# Saules_kolektoriaus_valdiklis_v1_21.net
KiCad netlist of a schematic drawn in EAGLE
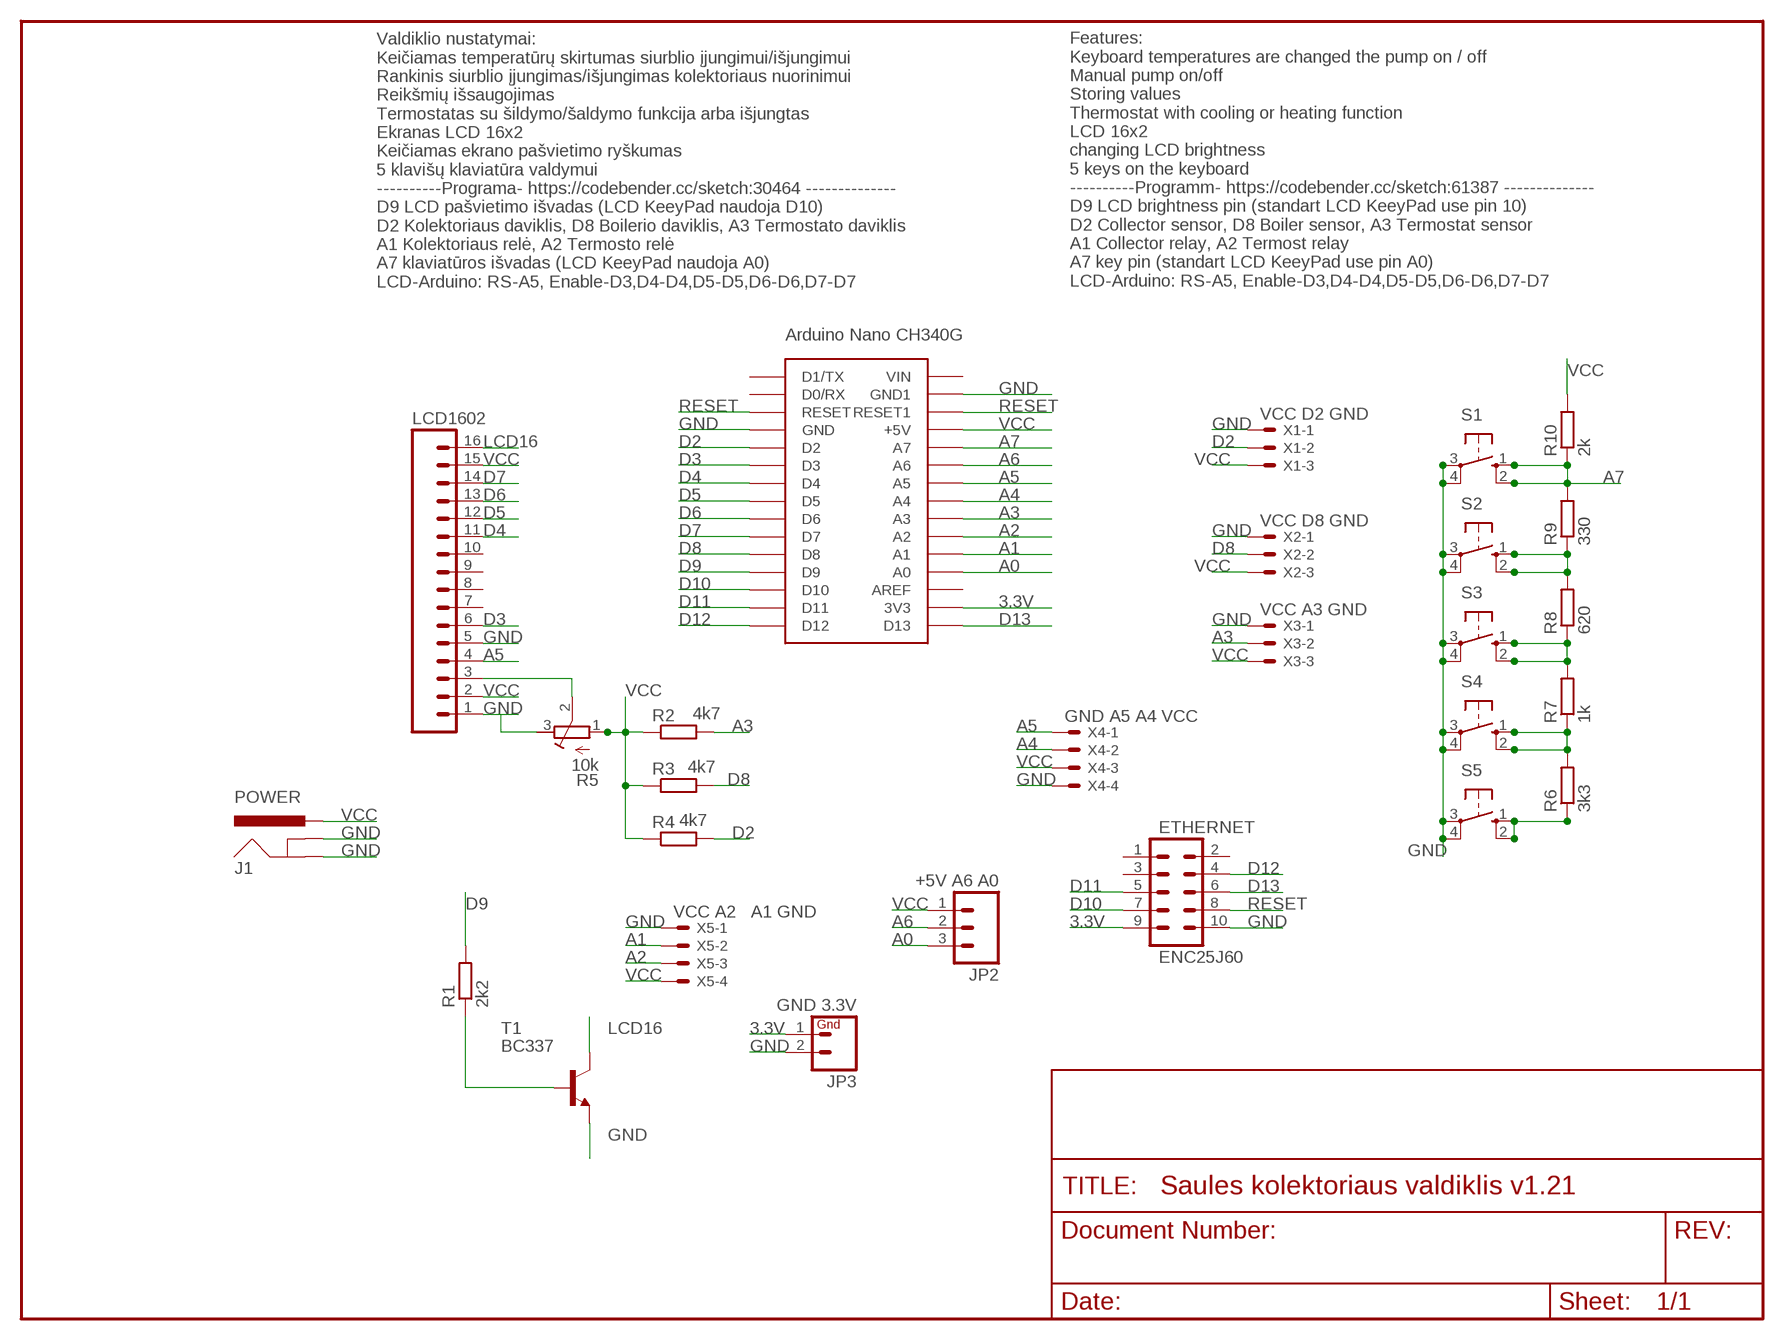
[diagram p0: schematic, sheet 1]

(export (version "E")
  (design (tool "Eeschema 10.0.6"))
  (components
    (comp (ref "ARDUINONANOCH340G")
      (value "ARDUINONANO")
      (footprint "eagle-import:PDIP-32")
      (libsource (lib "eagle-import") (part "ARDUINONANO"))
    )
    (comp (ref "ETHERNET")
      (value "ENC25J60")
      (footprint "eagle-import:AVR_ICSP")
      (libsource (lib "eagle-import") (part "M05X2PTH"))
    )
    (comp (ref "J1")
      (value "POWER")
      (footprint "eagle-import:POWER_JACK_PTH_LOCK")
      (libsource (lib "eagle-import") (part "POWER_JACKPTH_LOCK"))
    )
    (comp (ref "JP2")
      (value "+5V A6 A0")
      (footprint "eagle-import:1X03")
      (libsource (lib "eagle-import") (part "M03PTH"))
    )
    (comp (ref "JP3")
      (value "GND 3.3V")
      (footprint "eagle-import:1X02")
      (libsource (lib "eagle-import") (part "M02PTH"))
    )
    (comp (ref "LCD1602")
      (value "HEADER-16P-2.54")
      (footprint "eagle-import:16P-2.54")
      (libsource (lib "eagle-import") (part "HEADER-16P-2.54"))
    )
    (comp (ref "R1")
      (value "2k2")
      (footprint "eagle-import:0207_10")
      (libsource (lib "eagle-import") (part "R-EU_0207/10"))
    )
    (comp (ref "R2")
      (value "4k7")
      (footprint "eagle-import:0207_10")
      (libsource (lib "eagle-import") (part "R-EU_0207/10"))
    )
    (comp (ref "R3")
      (value "4k7")
      (footprint "eagle-import:0207_10")
      (libsource (lib "eagle-import") (part "R-EU_0207/10"))
    )
    (comp (ref "R4")
      (value "4k7")
      (footprint "eagle-import:0207_10")
      (libsource (lib "eagle-import") (part "R-EU_0207/10"))
    )
    (comp (ref "R5")
      (value "10k")
      (footprint "eagle-import:RTRIM64W")
      (libsource (lib "eagle-import") (part "R-TRIMM64W"))
    )
    (comp (ref "R6")
      (value "3k3")
      (footprint "eagle-import:0207_10")
      (libsource (lib "eagle-import") (part "R-EU_0207/10"))
    )
    (comp (ref "R7")
      (value "1k")
      (footprint "eagle-import:0207_10")
      (libsource (lib "eagle-import") (part "R-EU_0207/10"))
    )
    (comp (ref "R8")
      (value "620")
      (footprint "eagle-import:0207_10")
      (libsource (lib "eagle-import") (part "R-EU_0207/10"))
    )
    (comp (ref "R9")
      (value "330")
      (footprint "eagle-import:0207_10")
      (libsource (lib "eagle-import") (part "R-EU_0207/10"))
    )
    (comp (ref "R10")
      (value "2k")
      (footprint "eagle-import:0207_10")
      (libsource (lib "eagle-import") (part "R-EU_0207/10"))
    )
    (comp (ref "S1")
      (value "10-XX")
      (footprint "eagle-import:B3F-10XX")
      (fields (field (name "MPN") "B3F-1000"))
      (libsource (lib "eagle-import") (part "10-XX"))
    )
    (comp (ref "S2")
      (value "10-XX")
      (footprint "eagle-import:B3F-10XX")
      (fields (field (name "MPN") "B3F-1000"))
      (libsource (lib "eagle-import") (part "10-XX"))
    )
    (comp (ref "S3")
      (value "10-XX")
      (footprint "eagle-import:B3F-10XX")
      (fields (field (name "MPN") "B3F-1000"))
      (libsource (lib "eagle-import") (part "10-XX"))
    )
    (comp (ref "S4")
      (value "10-XX")
      (footprint "eagle-import:B3F-10XX")
      (fields (field (name "MPN") "B3F-1000"))
      (libsource (lib "eagle-import") (part "10-XX"))
    )
    (comp (ref "S5")
      (value "10-XX")
      (footprint "eagle-import:B3F-10XX")
      (fields (field (name "MPN") "B3F-1000"))
      (libsource (lib "eagle-import") (part "10-XX"))
    )
    (comp (ref "T1")
      (value "BC337")
      (footprint "eagle-import:TO92")
      (libsource (lib "eagle-import") (part "BC337"))
    )
    (comp (ref "X1")
      (value "VCC D2 GND")
      (footprint "eagle-import:22-23-2031")
      (fields (field (name "MF") "MOLEX") (field (name "MPN") "22-23-2031"))
      (libsource (lib "eagle-import") (part "22-23-2031"))
    )
    (comp (ref "X2")
      (value "VCC D8 GND")
      (footprint "eagle-import:22-23-2031")
      (fields (field (name "MF") "MOLEX") (field (name "MPN") "22-23-2031"))
      (libsource (lib "eagle-import") (part "22-23-2031"))
    )
    (comp (ref "X3")
      (value "VCC A3 GND")
      (footprint "eagle-import:22-23-2031")
      (fields (field (name "MF") "MOLEX") (field (name "MPN") "22-23-2031"))
      (libsource (lib "eagle-import") (part "22-23-2031"))
    )
    (comp (ref "X4")
      (value "GND A5 A4 VCC")
      (footprint "eagle-import:22-23-2041")
      (fields (field (name "MF") "MOLEX") (field (name "MPN") "22-23-2041"))
      (libsource (lib "eagle-import") (part "22-23-2041"))
    )
    (comp (ref "X5")
      (value "VCC A2 A1 GND")
      (footprint "eagle-import:22-23-2041")
      (fields (field (name "MF") "MOLEX") (field (name "MPN") "22-23-2041"))
      (libsource (lib "eagle-import") (part "22-23-2041"))
    )
  )
  (nets
    (net (code "1") (name "/3.3V") (class "Default")
      (node (ref "ARDUINONANOCH340G") (pin "3V3") (pinfunction "3V3_3V3") (pintype "bidirectional"))
      (node (ref "ETHERNET") (pin "9") (pinfunction "9_9") (pintype "passive"))
      (node (ref "JP3") (pin "1") (pinfunction "1_1") (pintype "passive"))
    )
    (net (code "2") (name "/A0") (class "Default")
      (node (ref "ARDUINONANOCH340G") (pin "A0") (pinfunction "A0_A0") (pintype "bidirectional"))
      (node (ref "JP2") (pin "3") (pinfunction "3_3") (pintype "passive"))
    )
    (net (code "3") (name "/A1") (class "Default")
      (node (ref "ARDUINONANOCH340G") (pin "A1") (pinfunction "A1_A1") (pintype "bidirectional"))
      (node (ref "X5") (pin "2") (pinfunction "S_2") (pintype "passive"))
    )
    (net (code "4") (name "/A2") (class "Default")
      (node (ref "ARDUINONANOCH340G") (pin "A2") (pinfunction "A2_A2") (pintype "bidirectional"))
      (node (ref "X5") (pin "3") (pinfunction "S_3") (pintype "passive"))
    )
    (net (code "5") (name "/A3") (class "Default")
      (node (ref "ARDUINONANOCH340G") (pin "A3") (pinfunction "A3_A3") (pintype "bidirectional"))
      (node (ref "R2") (pin "2") (pinfunction "2_2") (pintype "passive"))
      (node (ref "X3") (pin "2") (pinfunction "S_2") (pintype "passive"))
    )
    (net (code "6") (name "/A4") (class "Default")
      (node (ref "ARDUINONANOCH340G") (pin "A4") (pinfunction "A4_A4") (pintype "bidirectional"))
      (node (ref "X4") (pin "2") (pinfunction "S_2") (pintype "passive"))
    )
    (net (code "7") (name "/A5") (class "Default")
      (node (ref "ARDUINONANOCH340G") (pin "A5") (pinfunction "A5_A5") (pintype "bidirectional"))
      (node (ref "LCD1602") (pin "4") (pinfunction "4_4") (pintype "passive"))
      (node (ref "X4") (pin "1") (pinfunction "S_1") (pintype "passive"))
    )
    (net (code "8") (name "/A6") (class "Default")
      (node (ref "ARDUINONANOCH340G") (pin "A6") (pinfunction "A6_A6") (pintype "bidirectional"))
      (node (ref "JP2") (pin "2") (pinfunction "2_2") (pintype "passive"))
    )
    (net (code "9") (name "/A7") (class "Default")
      (node (ref "ARDUINONANOCH340G") (pin "A7") (pinfunction "A7_A7") (pintype "bidirectional"))
      (node (ref "R10") (pin "1") (pinfunction "1_1") (pintype "passive"))
      (node (ref "R9") (pin "2") (pinfunction "2_2") (pintype "passive"))
      (node (ref "S1") (pin "1") (pinfunction "S_1") (pintype "passive"))
      (node (ref "S1") (pin "2") (pinfunction "S1_2") (pintype "passive"))
    )
    (net (code "10") (name "/D2") (class "Default")
      (node (ref "ARDUINONANOCH340G") (pin "D2") (pinfunction "D2_D2") (pintype "bidirectional"))
      (node (ref "R4") (pin "2") (pinfunction "2_2") (pintype "passive"))
      (node (ref "X1") (pin "2") (pinfunction "S_2") (pintype "passive"))
    )
    (net (code "11") (name "/D3") (class "Default")
      (node (ref "ARDUINONANOCH340G") (pin "D3") (pinfunction "D3_D3") (pintype "bidirectional"))
      (node (ref "LCD1602") (pin "6") (pinfunction "6_6") (pintype "passive"))
    )
    (net (code "12") (name "/D4") (class "Default")
      (node (ref "ARDUINONANOCH340G") (pin "D4") (pinfunction "D4_D4") (pintype "bidirectional"))
      (node (ref "LCD1602") (pin "11") (pinfunction "11_11") (pintype "passive"))
    )
    (net (code "13") (name "/D5") (class "Default")
      (node (ref "ARDUINONANOCH340G") (pin "D5") (pinfunction "D5_D5") (pintype "bidirectional"))
      (node (ref "LCD1602") (pin "12") (pinfunction "12_12") (pintype "passive"))
    )
    (net (code "14") (name "/D6") (class "Default")
      (node (ref "ARDUINONANOCH340G") (pin "D6") (pinfunction "D6_D6") (pintype "bidirectional"))
      (node (ref "LCD1602") (pin "13") (pinfunction "13_13") (pintype "passive"))
    )
    (net (code "15") (name "/D7") (class "Default")
      (node (ref "ARDUINONANOCH340G") (pin "D7") (pinfunction "D7_D7") (pintype "bidirectional"))
      (node (ref "LCD1602") (pin "14") (pinfunction "14_14") (pintype "passive"))
    )
    (net (code "16") (name "/D8") (class "Default")
      (node (ref "ARDUINONANOCH340G") (pin "D8") (pinfunction "D8_D8") (pintype "bidirectional"))
      (node (ref "R3") (pin "2") (pinfunction "2_2") (pintype "passive"))
      (node (ref "X2") (pin "2") (pinfunction "S_2") (pintype "passive"))
    )
    (net (code "17") (name "/D9") (class "Default")
      (node (ref "ARDUINONANOCH340G") (pin "D9") (pinfunction "D9_D9") (pintype "bidirectional"))
      (node (ref "R1") (pin "2") (pinfunction "2_2") (pintype "passive"))
    )
    (net (code "18") (name "/D10") (class "Default")
      (node (ref "ARDUINONANOCH340G") (pin "D10") (pinfunction "D10_D10") (pintype "bidirectional"))
      (node (ref "ETHERNET") (pin "7") (pinfunction "7_7") (pintype "passive"))
    )
    (net (code "19") (name "/D11") (class "Default")
      (node (ref "ARDUINONANOCH340G") (pin "D11") (pinfunction "D11_D11") (pintype "bidirectional"))
      (node (ref "ETHERNET") (pin "5") (pinfunction "5_5") (pintype "passive"))
    )
    (net (code "20") (name "/D12") (class "Default")
      (node (ref "ARDUINONANOCH340G") (pin "D12") (pinfunction "D12_D12") (pintype "bidirectional"))
      (node (ref "ETHERNET") (pin "4") (pinfunction "4_4") (pintype "passive"))
    )
    (net (code "21") (name "/D13") (class "Default")
      (node (ref "ARDUINONANOCH340G") (pin "D13") (pinfunction "D13_D13") (pintype "bidirectional"))
      (node (ref "ETHERNET") (pin "6") (pinfunction "6_6") (pintype "passive"))
    )
    (net (code "22") (name "/GND") (class "Default")
      (node (ref "ARDUINONANOCH340G") (pin "GND") (pinfunction "GND_GND") (pintype "bidirectional"))
      (node (ref "ARDUINONANOCH340G") (pin "GND1") (pinfunction "GND1_GND1") (pintype "bidirectional"))
      (node (ref "ETHERNET") (pin "10") (pinfunction "10_10") (pintype "passive"))
      (node (ref "J1") (pin "GND") (pinfunction "GND_GND") (pintype "bidirectional"))
      (node (ref "J1") (pin "GNDBREAK") (pinfunction "GNDBREAK_GNDBREAK") (pintype "bidirectional"))
      (node (ref "JP3") (pin "2") (pinfunction "2_2") (pintype "passive"))
      (node (ref "LCD1602") (pin "1") (pinfunction "1_1") (pintype "passive"))
      (node (ref "LCD1602") (pin "5") (pinfunction "5_5") (pintype "passive"))
      (node (ref "R5") (pin "3") (pinfunction "A_3") (pintype "passive"))
      (node (ref "S1") (pin "3") (pinfunction "P_3") (pintype "passive"))
      (node (ref "S1") (pin "4") (pinfunction "P1_4") (pintype "passive"))
      (node (ref "S2") (pin "3") (pinfunction "P_3") (pintype "passive"))
      (node (ref "S2") (pin "4") (pinfunction "P1_4") (pintype "passive"))
      (node (ref "S3") (pin "3") (pinfunction "P_3") (pintype "passive"))
      (node (ref "S3") (pin "4") (pinfunction "P1_4") (pintype "passive"))
      (node (ref "S4") (pin "3") (pinfunction "P_3") (pintype "passive"))
      (node (ref "S4") (pin "4") (pinfunction "P1_4") (pintype "passive"))
      (node (ref "S5") (pin "3") (pinfunction "P_3") (pintype "passive"))
      (node (ref "S5") (pin "4") (pinfunction "P1_4") (pintype "passive"))
      (node (ref "T1") (pin "1") (pinfunction "E_1") (pintype "passive"))
      (node (ref "X1") (pin "1") (pinfunction "S_1") (pintype "passive"))
      (node (ref "X2") (pin "1") (pinfunction "S_1") (pintype "passive"))
      (node (ref "X3") (pin "1") (pinfunction "S_1") (pintype "passive"))
      (node (ref "X4") (pin "4") (pinfunction "S_4") (pintype "passive"))
      (node (ref "X5") (pin "1") (pinfunction "S_1") (pintype "passive"))
    )
    (net (code "23") (name "/LCD16") (class "Default")
      (node (ref "LCD1602") (pin "16") (pinfunction "16_16") (pintype "passive"))
      (node (ref "T1") (pin "3") (pinfunction "C_3") (pintype "passive"))
    )
    (net (code "24") (name "/RESET") (class "Default")
      (node (ref "ARDUINONANOCH340G") (pin "RESET") (pinfunction "RESET_RESET") (pintype "bidirectional"))
      (node (ref "ARDUINONANOCH340G") (pin "RESET1") (pinfunction "RESET1_RESET1") (pintype "bidirectional"))
      (node (ref "ETHERNET") (pin "8") (pinfunction "8_8") (pintype "passive"))
    )
    (net (code "25") (name "/VCC") (class "Default")
      (node (ref "ARDUINONANOCH340G") (pin "+5V") (pinfunction "+5V_+5V") (pintype "bidirectional"))
      (node (ref "J1") (pin "PWR") (pinfunction "PWR_PWR") (pintype "bidirectional"))
      (node (ref "JP2") (pin "1") (pinfunction "1_1") (pintype "passive"))
      (node (ref "LCD1602") (pin "15") (pinfunction "15_15") (pintype "passive"))
      (node (ref "LCD1602") (pin "2") (pinfunction "2_2") (pintype "passive"))
      (node (ref "R10") (pin "2") (pinfunction "2_2") (pintype "passive"))
      (node (ref "R2") (pin "1") (pinfunction "1_1") (pintype "passive"))
      (node (ref "R3") (pin "1") (pinfunction "1_1") (pintype "passive"))
      (node (ref "R4") (pin "1") (pinfunction "1_1") (pintype "passive"))
      (node (ref "R5") (pin "1") (pinfunction "E_1") (pintype "passive"))
      (node (ref "X1") (pin "3") (pinfunction "S_3") (pintype "passive"))
      (node (ref "X2") (pin "3") (pinfunction "S_3") (pintype "passive"))
      (node (ref "X3") (pin "3") (pinfunction "S_3") (pintype "passive"))
      (node (ref "X4") (pin "3") (pinfunction "S_3") (pintype "passive"))
      (node (ref "X5") (pin "4") (pinfunction "S_4") (pintype "passive"))
    )
    (net (code "26") (name "Net-(R5-S)") (class "Default")
      (node (ref "LCD1602") (pin "3") (pinfunction "3_3") (pintype "passive"))
      (node (ref "R5") (pin "2") (pinfunction "S_2") (pintype "passive"))
    )
    (net (code "27") (name "Net-(S2-S)") (class "Default")
      (node (ref "R8") (pin "2") (pinfunction "2_2") (pintype "passive"))
      (node (ref "R9") (pin "1") (pinfunction "1_1") (pintype "passive"))
      (node (ref "S2") (pin "1") (pinfunction "S_1") (pintype "passive"))
      (node (ref "S2") (pin "2") (pinfunction "S1_2") (pintype "passive"))
    )
    (net (code "28") (name "Net-(S3-S)") (class "Default")
      (node (ref "R7") (pin "2") (pinfunction "2_2") (pintype "passive"))
      (node (ref "R8") (pin "1") (pinfunction "1_1") (pintype "passive"))
      (node (ref "S3") (pin "1") (pinfunction "S_1") (pintype "passive"))
      (node (ref "S3") (pin "2") (pinfunction "S1_2") (pintype "passive"))
    )
    (net (code "29") (name "Net-(S4-S)") (class "Default")
      (node (ref "R6") (pin "2") (pinfunction "2_2") (pintype "passive"))
      (node (ref "R7") (pin "1") (pinfunction "1_1") (pintype "passive"))
      (node (ref "S4") (pin "1") (pinfunction "S_1") (pintype "passive"))
      (node (ref "S4") (pin "2") (pinfunction "S1_2") (pintype "passive"))
    )
    (net (code "30") (name "Net-(S5-S)") (class "Default")
      (node (ref "R6") (pin "1") (pinfunction "1_1") (pintype "passive"))
      (node (ref "S5") (pin "1") (pinfunction "S_1") (pintype "passive"))
      (node (ref "S5") (pin "2") (pinfunction "S1_2") (pintype "passive"))
    )
    (net (code "31") (name "Net-(T1-B)") (class "Default")
      (node (ref "R1") (pin "1") (pinfunction "1_1") (pintype "passive"))
      (node (ref "T1") (pin "2") (pinfunction "B_2") (pintype "passive"))
    )
    (net (code "32") (name "unconnected-(ARDUINONANOCH340G-PadAREF)") (class "Default")
      (node (ref "ARDUINONANOCH340G") (pin "AREF") (pinfunction "AREF_AREF") (pintype "bidirectional"))
    )
    (net (code "33") (name "unconnected-(ARDUINONANOCH340G-PadD0{slash}RX)") (class "Default")
      (node (ref "ARDUINONANOCH340G") (pin "D0/RX") (pinfunction "D0/RX_D0/RX") (pintype "bidirectional"))
    )
    (net (code "34") (name "unconnected-(ARDUINONANOCH340G-PadD1{slash}TX)") (class "Default")
      (node (ref "ARDUINONANOCH340G") (pin "D1/TX") (pinfunction "D1/TX_D1/TX") (pintype "bidirectional"))
    )
    (net (code "35") (name "unconnected-(ARDUINONANOCH340G-PadVIN)") (class "Default")
      (node (ref "ARDUINONANOCH340G") (pin "VIN") (pinfunction "VIN_VIN") (pintype "bidirectional"))
    )
    (net (code "36") (name "unconnected-(ETHERNET-Pad1)") (class "Default")
      (node (ref "ETHERNET") (pin "1") (pinfunction "1_1") (pintype "passive"))
    )
    (net (code "37") (name "unconnected-(ETHERNET-Pad2)") (class "Default")
      (node (ref "ETHERNET") (pin "2") (pinfunction "2_2") (pintype "passive"))
    )
    (net (code "38") (name "unconnected-(ETHERNET-Pad3)") (class "Default")
      (node (ref "ETHERNET") (pin "3") (pinfunction "3_3") (pintype "passive"))
    )
    (net (code "39") (name "unconnected-(LCD1602-Pad7)") (class "Default")
      (node (ref "LCD1602") (pin "7") (pinfunction "7_7") (pintype "passive"))
    )
    (net (code "40") (name "unconnected-(LCD1602-Pad8)") (class "Default")
      (node (ref "LCD1602") (pin "8") (pinfunction "8_8") (pintype "passive"))
    )
    (net (code "41") (name "unconnected-(LCD1602-Pad9)") (class "Default")
      (node (ref "LCD1602") (pin "9") (pinfunction "9_9") (pintype "passive"))
    )
    (net (code "42") (name "unconnected-(LCD1602-Pad10)") (class "Default")
      (node (ref "LCD1602") (pin "10") (pinfunction "10_10") (pintype "passive"))
    )
  )
)
